# telemetry_adc.net
KiCad netlist of a schematic drawn in Altium Designer
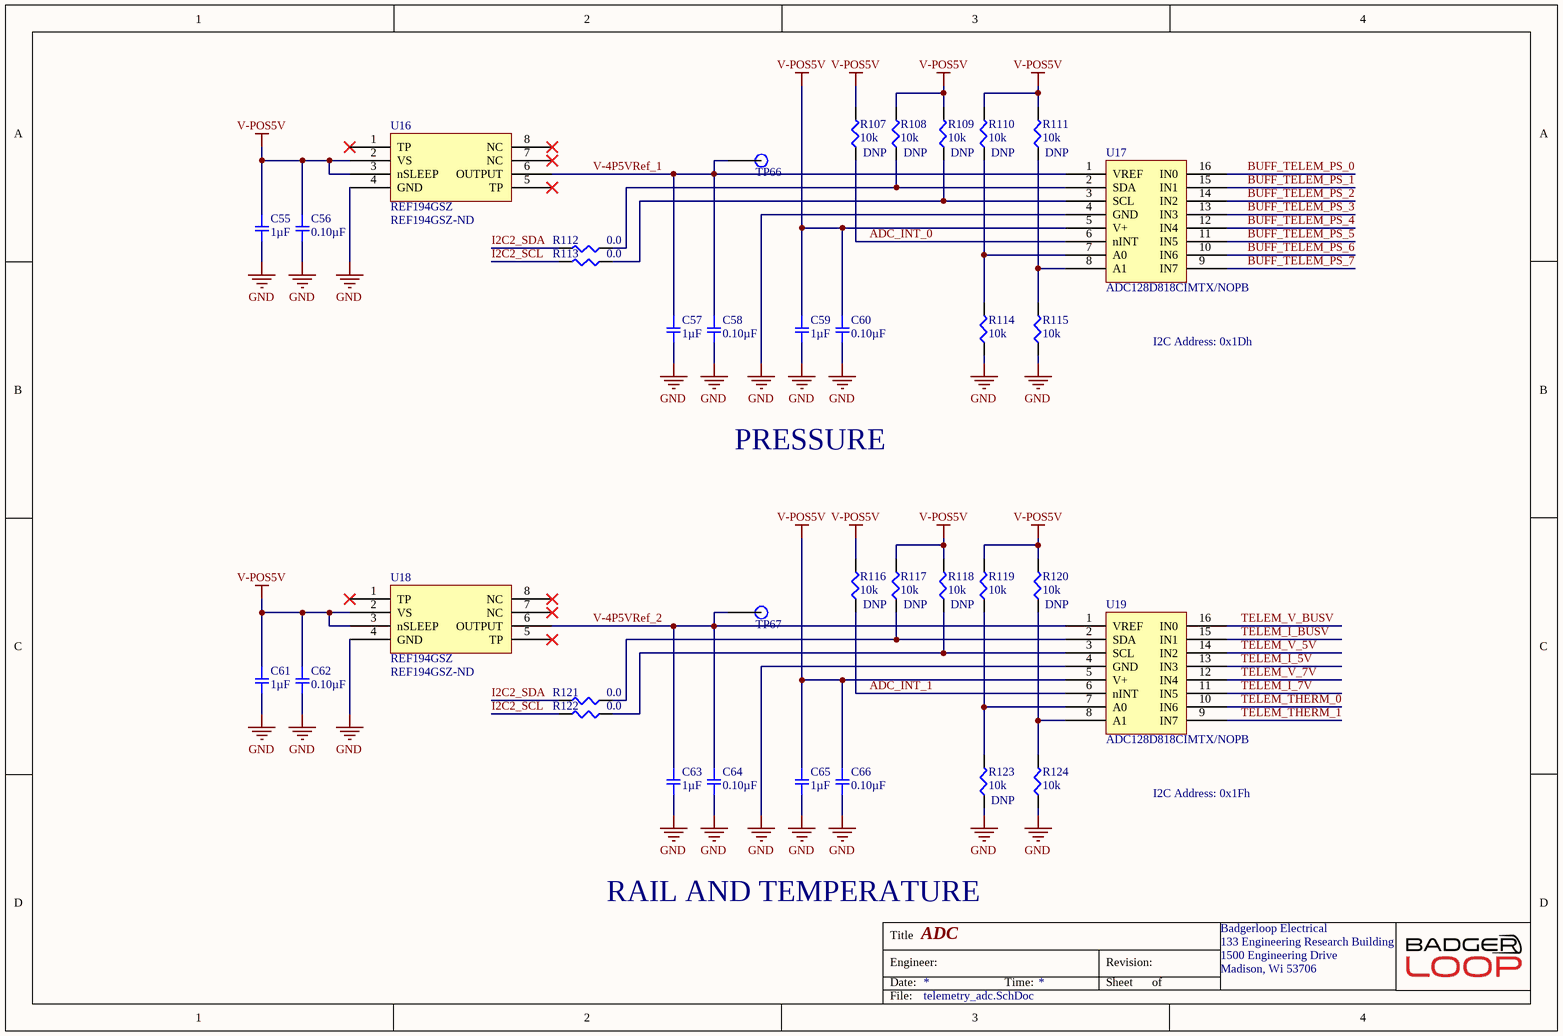
[diagram p0: telemetry_adc.SchDoc]

(export (version "E")
  (design (tool "Eeschema 10.0.6"))
  (components
    (comp (ref "C55")
      (value "1µF")
      (footprint "SMD-0805C")
      (description "CAP CER 1UF 50V X7R 0805")
      (fields
        (field (name "DIGI-KEY PART NUMBER") "490-4736-1-ND")
        (field (name "PART NUMBER") "GRM21BR71H105KA12L")
      )
      (libsource (lib "capacitors") (part "GRM21BR71H105KA12L"))
    )
    (comp (ref "C56")
      (value "0.10µF")
      (footprint "SMD-0805C")
      (description "CAP CER 0.1UF 50V X7R 0805")
      (fields
        (field (name "DIGI-KEY PART NUMBER") "490-11955-1-ND")
        (field (name "PART NUMBER") "GCD21BR71H104KA01L")
      )
      (libsource (lib "capacitors") (part "GCD21BR71H104KA01L"))
    )
    (comp (ref "C57")
      (value "1µF")
      (footprint "SMD-0805C")
      (description "CAP CER 1UF 50V X7R 0805")
      (fields
        (field (name "DIGI-KEY PART NUMBER") "490-4736-1-ND")
        (field (name "PART NUMBER") "GRM21BR71H105KA12L")
      )
      (libsource (lib "capacitors") (part "GRM21BR71H105KA12L"))
    )
    (comp (ref "C58")
      (value "0.10µF")
      (footprint "SMD-0805C")
      (description "CAP CER 0.1UF 50V X7R 0805")
      (fields
        (field (name "DIGI-KEY PART NUMBER") "490-11955-1-ND")
        (field (name "PART NUMBER") "GCD21BR71H104KA01L")
      )
      (libsource (lib "capacitors") (part "GCD21BR71H104KA01L"))
    )
    (comp (ref "C59")
      (value "1µF")
      (footprint "SMD-0805C")
      (description "CAP CER 1UF 50V X7R 0805")
      (fields
        (field (name "DIGI-KEY PART NUMBER") "490-4736-1-ND")
        (field (name "PART NUMBER") "GRM21BR71H105KA12L")
      )
      (libsource (lib "capacitors") (part "GRM21BR71H105KA12L"))
    )
    (comp (ref "C60")
      (value "0.10µF")
      (footprint "SMD-0805C")
      (description "CAP CER 0.1UF 50V X7R 0805")
      (fields
        (field (name "DIGI-KEY PART NUMBER") "490-11955-1-ND")
        (field (name "PART NUMBER") "GCD21BR71H104KA01L")
      )
      (libsource (lib "capacitors") (part "GCD21BR71H104KA01L"))
    )
    (comp (ref "C61")
      (value "1µF")
      (footprint "SMD-0805C")
      (description "CAP CER 1UF 50V X7R 0805")
      (fields
        (field (name "DIGI-KEY PART NUMBER") "490-4736-1-ND")
        (field (name "PART NUMBER") "GRM21BR71H105KA12L")
      )
      (libsource (lib "capacitors") (part "GRM21BR71H105KA12L"))
    )
    (comp (ref "C62")
      (value "0.10µF")
      (footprint "SMD-0805C")
      (description "CAP CER 0.1UF 50V X7R 0805")
      (fields
        (field (name "DIGI-KEY PART NUMBER") "490-11955-1-ND")
        (field (name "PART NUMBER") "GCD21BR71H104KA01L")
      )
      (libsource (lib "capacitors") (part "GCD21BR71H104KA01L"))
    )
    (comp (ref "C63")
      (value "1µF")
      (footprint "SMD-0805C")
      (description "CAP CER 1UF 50V X7R 0805")
      (fields
        (field (name "DIGI-KEY PART NUMBER") "490-4736-1-ND")
        (field (name "PART NUMBER") "GRM21BR71H105KA12L")
      )
      (libsource (lib "capacitors") (part "GRM21BR71H105KA12L"))
    )
    (comp (ref "C64")
      (value "0.10µF")
      (footprint "SMD-0805C")
      (description "CAP CER 0.1UF 50V X7R 0805")
      (fields
        (field (name "DIGI-KEY PART NUMBER") "490-11955-1-ND")
        (field (name "PART NUMBER") "GCD21BR71H104KA01L")
      )
      (libsource (lib "capacitors") (part "GCD21BR71H104KA01L"))
    )
    (comp (ref "C65")
      (value "1µF")
      (footprint "SMD-0805C")
      (description "CAP CER 1UF 50V X7R 0805")
      (fields
        (field (name "DIGI-KEY PART NUMBER") "490-4736-1-ND")
        (field (name "PART NUMBER") "GRM21BR71H105KA12L")
      )
      (libsource (lib "capacitors") (part "GRM21BR71H105KA12L"))
    )
    (comp (ref "C66")
      (value "0.10µF")
      (footprint "SMD-0805C")
      (description "CAP CER 0.1UF 50V X7R 0805")
      (fields
        (field (name "DIGI-KEY PART NUMBER") "490-11955-1-ND")
        (field (name "PART NUMBER") "GCD21BR71H104KA01L")
      )
      (libsource (lib "capacitors") (part "GCD21BR71H104KA01L"))
    )
    (comp (ref "R107")
      (value "10k")
      (footprint "SMD-0805-RES")
      (description "RES SMD 10K OHM 5% 1/2W 0805")
      (fields
        (field (name "PART NUMBER") "ERJ-P06J103V")
        (field (name "DIGI-KEY PART NUMBER") "P10KADCT-ND")
        (field (name "DNP") "DNP")
      )
      (libsource (lib "resistors") (part "ERJ-P06J103V"))
    )
    (comp (ref "R108")
      (value "10k")
      (footprint "SMD-0805-RES")
      (description "RES SMD 10K OHM 5% 1/2W 0805")
      (fields
        (field (name "PART NUMBER") "ERJ-P06J103V")
        (field (name "DIGI-KEY PART NUMBER") "P10KADCT-ND")
        (field (name "DNP") "DNP")
      )
      (libsource (lib "resistors") (part "ERJ-P06J103V"))
    )
    (comp (ref "R109")
      (value "10k")
      (footprint "SMD-0805-RES")
      (description "RES SMD 10K OHM 5% 1/2W 0805")
      (fields
        (field (name "PART NUMBER") "ERJ-P06J103V")
        (field (name "DIGI-KEY PART NUMBER") "P10KADCT-ND")
        (field (name "DNP") "DNP")
      )
      (libsource (lib "resistors") (part "ERJ-P06J103V"))
    )
    (comp (ref "R110")
      (value "10k")
      (footprint "SMD-0805-RES")
      (description "RES SMD 10K OHM 5% 1/2W 0805")
      (fields
        (field (name "PART NUMBER") "ERJ-P06J103V")
        (field (name "DIGI-KEY PART NUMBER") "P10KADCT-ND")
        (field (name "DNP") "DNP")
      )
      (libsource (lib "resistors") (part "ERJ-P06J103V"))
    )
    (comp (ref "R111")
      (value "10k")
      (footprint "SMD-0805-RES")
      (description "RES SMD 10K OHM 5% 1/2W 0805")
      (fields
        (field (name "PART NUMBER") "ERJ-P06J103V")
        (field (name "DIGI-KEY PART NUMBER") "P10KADCT-ND")
        (field (name "DNP") "DNP")
      )
      (libsource (lib "resistors") (part "ERJ-P06J103V"))
    )
    (comp (ref "R112")
      (value "0.0")
      (footprint "SMD-0805-RES")
      (description "RES SMD 0.0 OHM JUMPER 1/8W 0805")
      (fields (field (name "PART NUMBER") "ERJ-6GEY0R00V") (field (name "DIGI-KEY PART NUMBER") "P0.0ACT-ND"))
      (libsource (lib "resistors") (part "ERJ-6GEY0R00V"))
    )
    (comp (ref "R113")
      (value "0.0")
      (footprint "SMD-0805-RES")
      (description "RES SMD 0.0 OHM JUMPER 1/8W 0805")
      (fields (field (name "PART NUMBER") "ERJ-6GEY0R00V") (field (name "DIGI-KEY PART NUMBER") "P0.0ACT-ND"))
      (libsource (lib "resistors") (part "ERJ-6GEY0R00V"))
    )
    (comp (ref "R114")
      (value "10k")
      (footprint "SMD-0805-RES")
      (description "RES SMD 10K OHM 5% 1/2W 0805")
      (fields (field (name "PART NUMBER") "ERJ-P06J103V") (field (name "DIGI-KEY PART NUMBER") "P10KADCT-ND"))
      (libsource (lib "resistors") (part "ERJ-P06J103V"))
    )
    (comp (ref "R115")
      (value "10k")
      (footprint "SMD-0805-RES")
      (description "RES SMD 10K OHM 5% 1/2W 0805")
      (fields (field (name "PART NUMBER") "ERJ-P06J103V") (field (name "DIGI-KEY PART NUMBER") "P10KADCT-ND"))
      (libsource (lib "resistors") (part "ERJ-P06J103V"))
    )
    (comp (ref "R116")
      (value "10k")
      (footprint "SMD-0805-RES")
      (description "RES SMD 10K OHM 5% 1/2W 0805")
      (fields
        (field (name "PART NUMBER") "ERJ-P06J103V")
        (field (name "DIGI-KEY PART NUMBER") "P10KADCT-ND")
        (field (name "DNP") "DNP")
      )
      (libsource (lib "resistors") (part "ERJ-P06J103V"))
    )
    (comp (ref "R117")
      (value "10k")
      (footprint "SMD-0805-RES")
      (description "RES SMD 10K OHM 5% 1/2W 0805")
      (fields
        (field (name "PART NUMBER") "ERJ-P06J103V")
        (field (name "DIGI-KEY PART NUMBER") "P10KADCT-ND")
        (field (name "DNP") "DNP")
      )
      (libsource (lib "resistors") (part "ERJ-P06J103V"))
    )
    (comp (ref "R118")
      (value "10k")
      (footprint "SMD-0805-RES")
      (description "RES SMD 10K OHM 5% 1/2W 0805")
      (fields
        (field (name "PART NUMBER") "ERJ-P06J103V")
        (field (name "DIGI-KEY PART NUMBER") "P10KADCT-ND")
        (field (name "DNP") "DNP")
      )
      (libsource (lib "resistors") (part "ERJ-P06J103V"))
    )
    (comp (ref "R119")
      (value "10k")
      (footprint "SMD-0805-RES")
      (description "RES SMD 10K OHM 5% 1/2W 0805")
      (fields (field (name "PART NUMBER") "ERJ-P06J103V") (field (name "DIGI-KEY PART NUMBER") "P10KADCT-ND"))
      (libsource (lib "resistors") (part "ERJ-P06J103V"))
    )
    (comp (ref "R120")
      (value "10k")
      (footprint "SMD-0805-RES")
      (description "RES SMD 10K OHM 5% 1/2W 0805")
      (fields
        (field (name "PART NUMBER") "ERJ-P06J103V")
        (field (name "DIGI-KEY PART NUMBER") "P10KADCT-ND")
        (field (name "DNP") "DNP")
      )
      (libsource (lib "resistors") (part "ERJ-P06J103V"))
    )
    (comp (ref "R121")
      (value "0.0")
      (footprint "SMD-0805-RES")
      (description "RES SMD 0.0 OHM JUMPER 1/8W 0805")
      (fields (field (name "PART NUMBER") "ERJ-6GEY0R00V") (field (name "DIGI-KEY PART NUMBER") "P0.0ACT-ND"))
      (libsource (lib "resistors") (part "ERJ-6GEY0R00V"))
    )
    (comp (ref "R122")
      (value "0.0")
      (footprint "SMD-0805-RES")
      (description "RES SMD 0.0 OHM JUMPER 1/8W 0805")
      (fields (field (name "PART NUMBER") "ERJ-6GEY0R00V") (field (name "DIGI-KEY PART NUMBER") "P0.0ACT-ND"))
      (libsource (lib "resistors") (part "ERJ-6GEY0R00V"))
    )
    (comp (ref "R123")
      (value "10k")
      (footprint "SMD-0805-RES")
      (description "RES SMD 10K OHM 5% 1/2W 0805")
      (fields
        (field (name "PART NUMBER") "ERJ-P06J103V")
        (field (name "DIGI-KEY PART NUMBER") "P10KADCT-ND")
        (field (name "DNP") "DNP")
      )
      (libsource (lib "resistors") (part "ERJ-P06J103V"))
    )
    (comp (ref "R124")
      (value "10k")
      (footprint "SMD-0805-RES")
      (description "RES SMD 10K OHM 5% 1/2W 0805")
      (fields (field (name "PART NUMBER") "ERJ-P06J103V") (field (name "DIGI-KEY PART NUMBER") "P10KADCT-ND"))
      (libsource (lib "resistors") (part "ERJ-P06J103V"))
    )
    (comp (ref "TP66")
      (value "TP")
      (footprint "Test Point")
      (description "SMD TEST POINT")
      (libsource (lib "misc") (part "TP"))
    )
    (comp (ref "TP67")
      (value "TP")
      (footprint "Test Point")
      (description "SMD TEST POINT")
      (libsource (lib "misc") (part "TP"))
    )
    (comp (ref "U16")
      (value "REF194GSZ")
      (footprint "SOP127P600X175-8N")
      (description "IC VREF SERIES 4.5V 8SOIC")
      (fields
        (field (name "MANUFACTURER") "Analog Devices")
        (field (name "SUPPLIER PART NUMBER 1") "REF194GSZ-ND")
      )
      (libsource (lib "ic") (part "REF194GSZ"))
    )
    (comp (ref "U17")
      (value "ADC128D818CIMTX/NOPB")
      (footprint "TSOP65P660X120-16N")
      (description "Analog to Digital Converters - ADC")
      (fields (field (name "MANUFACTURER") "TI National Semiconductor"))
      (libsource (lib "ic") (part "ADC128D818CIMTX/NOPB"))
    )
    (comp (ref "U18")
      (value "REF194GSZ")
      (footprint "SOP127P600X175-8N")
      (description "IC VREF SERIES 4.5V 8SOIC")
      (fields
        (field (name "MANUFACTURER") "Analog Devices")
        (field (name "SUPPLIER PART NUMBER 1") "REF194GSZ-ND")
      )
      (libsource (lib "ic") (part "REF194GSZ"))
    )
    (comp (ref "U19")
      (value "ADC128D818CIMTX/NOPB")
      (footprint "TSOP65P660X120-16N")
      (description "Analog to Digital Converters - ADC")
      (fields (field (name "MANUFACTURER") "TI National Semiconductor"))
      (libsource (lib "ic") (part "ADC128D818CIMTX/NOPB"))
    )
  )
  (nets
    (net (code "1") (name "/ADC_INT_0") (class "Default")
      (node (ref "R107") (pin "1") (pinfunction "1_1") (pintype "passive"))
      (node (ref "U17") (pin "6") (pinfunction "nINT_6") (pintype "passive"))
    )
    (net (code "2") (name "/ADC_INT_1") (class "Default")
      (node (ref "R116") (pin "1") (pinfunction "1_1") (pintype "passive"))
      (node (ref "U19") (pin "6") (pinfunction "nINT_6") (pintype "passive"))
    )
    (net (code "3") (name "/BUFF_TELEM_PS_0") (class "Default")
      (node (ref "U17") (pin "16") (pinfunction "IN0_16") (pintype "passive"))
    )
    (net (code "4") (name "/BUFF_TELEM_PS_1") (class "Default")
      (node (ref "U17") (pin "15") (pinfunction "IN1_15") (pintype "passive"))
    )
    (net (code "5") (name "/BUFF_TELEM_PS_2") (class "Default")
      (node (ref "U17") (pin "14") (pinfunction "IN2_14") (pintype "passive"))
    )
    (net (code "6") (name "/BUFF_TELEM_PS_3") (class "Default")
      (node (ref "U17") (pin "13") (pinfunction "IN3_13") (pintype "passive"))
    )
    (net (code "7") (name "/BUFF_TELEM_PS_4") (class "Default")
      (node (ref "U17") (pin "12") (pinfunction "IN4_12") (pintype "passive"))
    )
    (net (code "8") (name "/BUFF_TELEM_PS_5") (class "Default")
      (node (ref "U17") (pin "11") (pinfunction "IN5_11") (pintype "passive"))
    )
    (net (code "9") (name "/BUFF_TELEM_PS_6") (class "Default")
      (node (ref "U17") (pin "10") (pinfunction "IN6_10") (pintype "passive"))
    )
    (net (code "10") (name "/BUFF_TELEM_PS_7") (class "Default")
      (node (ref "U17") (pin "9") (pinfunction "IN7_9") (pintype "passive"))
    )
    (net (code "11") (name "/I2C2_SCL") (class "Default")
      (node (ref "R113") (pin "2") (pinfunction "2_2") (pintype "passive"))
      (node (ref "R122") (pin "2") (pinfunction "2_2") (pintype "passive"))
    )
    (net (code "12") (name "/I2C2_SDA") (class "Default")
      (node (ref "R112") (pin "2") (pinfunction "2_2") (pintype "passive"))
      (node (ref "R121") (pin "2") (pinfunction "2_2") (pintype "passive"))
    )
    (net (code "13") (name "/TELEM_I_5V") (class "Default")
      (node (ref "U19") (pin "13") (pinfunction "IN3_13") (pintype "passive"))
    )
    (net (code "14") (name "/TELEM_I_7V") (class "Default")
      (node (ref "U19") (pin "11") (pinfunction "IN5_11") (pintype "passive"))
    )
    (net (code "15") (name "/TELEM_I_BUSV") (class "Default")
      (node (ref "U19") (pin "15") (pinfunction "IN1_15") (pintype "passive"))
    )
    (net (code "16") (name "/TELEM_THERM_0") (class "Default")
      (node (ref "U19") (pin "10") (pinfunction "IN6_10") (pintype "passive"))
    )
    (net (code "17") (name "/TELEM_THERM_1") (class "Default")
      (node (ref "U19") (pin "9") (pinfunction "IN7_9") (pintype "passive"))
    )
    (net (code "18") (name "/TELEM_V_5V") (class "Default")
      (node (ref "U19") (pin "14") (pinfunction "IN2_14") (pintype "passive"))
    )
    (net (code "19") (name "/TELEM_V_7V") (class "Default")
      (node (ref "U19") (pin "12") (pinfunction "IN4_12") (pintype "passive"))
    )
    (net (code "20") (name "/TELEM_V_BUSV") (class "Default")
      (node (ref "U19") (pin "16") (pinfunction "IN0_16") (pintype "passive"))
    )
    (net (code "21") (name "/V-4P5VRef_1") (class "Default")
      (node (ref "C57") (pin "1") (pinfunction "1_1") (pintype "passive"))
      (node (ref "C58") (pin "1") (pinfunction "1_1") (pintype "passive"))
      (node (ref "TP66") (pin "1") (pinfunction "1_1") (pintype "passive"))
      (node (ref "U16") (pin "6") (pinfunction "OUTPUT_6") (pintype "passive"))
      (node (ref "U17") (pin "1") (pinfunction "VREF_1") (pintype "passive"))
    )
    (net (code "22") (name "/V-4P5VRef_2") (class "Default")
      (node (ref "C63") (pin "1") (pinfunction "1_1") (pintype "passive"))
      (node (ref "C64") (pin "1") (pinfunction "1_1") (pintype "passive"))
      (node (ref "TP67") (pin "1") (pinfunction "1_1") (pintype "passive"))
      (node (ref "U18") (pin "6") (pinfunction "OUTPUT_6") (pintype "passive"))
      (node (ref "U19") (pin "1") (pinfunction "VREF_1") (pintype "passive"))
    )
    (net (code "23") (name "GND") (class "Default")
      (node (ref "C55") (pin "2") (pinfunction "2_2") (pintype "passive"))
      (node (ref "C56") (pin "2") (pinfunction "2_2") (pintype "passive"))
      (node (ref "C57") (pin "2") (pinfunction "2_2") (pintype "passive"))
      (node (ref "C58") (pin "2") (pinfunction "2_2") (pintype "passive"))
      (node (ref "C59") (pin "2") (pinfunction "2_2") (pintype "passive"))
      (node (ref "C60") (pin "2") (pinfunction "2_2") (pintype "passive"))
      (node (ref "C61") (pin "2") (pinfunction "2_2") (pintype "passive"))
      (node (ref "C62") (pin "2") (pinfunction "2_2") (pintype "passive"))
      (node (ref "C63") (pin "2") (pinfunction "2_2") (pintype "passive"))
      (node (ref "C64") (pin "2") (pinfunction "2_2") (pintype "passive"))
      (node (ref "C65") (pin "2") (pinfunction "2_2") (pintype "passive"))
      (node (ref "C66") (pin "2") (pinfunction "2_2") (pintype "passive"))
      (node (ref "R114") (pin "1") (pinfunction "1_1") (pintype "passive"))
      (node (ref "R115") (pin "1") (pinfunction "1_1") (pintype "passive"))
      (node (ref "R123") (pin "1") (pinfunction "1_1") (pintype "passive"))
      (node (ref "R124") (pin "1") (pinfunction "1_1") (pintype "passive"))
      (node (ref "U16") (pin "4") (pinfunction "GND_4") (pintype "passive"))
      (node (ref "U17") (pin "4") (pinfunction "GND_4") (pintype "passive"))
      (node (ref "U18") (pin "4") (pinfunction "GND_4") (pintype "passive"))
      (node (ref "U19") (pin "4") (pinfunction "GND_4") (pintype "passive"))
    )
    (net (code "24") (name "Net-(U17-A0)") (class "Default")
      (node (ref "R110") (pin "1") (pinfunction "1_1") (pintype "passive"))
      (node (ref "R114") (pin "2") (pinfunction "2_2") (pintype "passive"))
      (node (ref "U17") (pin "7") (pinfunction "A0_7") (pintype "passive"))
    )
    (net (code "25") (name "Net-(U17-A1)") (class "Default")
      (node (ref "R111") (pin "1") (pinfunction "1_1") (pintype "passive"))
      (node (ref "R115") (pin "2") (pinfunction "2_2") (pintype "passive"))
      (node (ref "U17") (pin "8") (pinfunction "A1_8") (pintype "passive"))
    )
    (net (code "26") (name "Net-(U17-SCL)") (class "Default")
      (node (ref "R109") (pin "1") (pinfunction "1_1") (pintype "passive"))
      (node (ref "R113") (pin "1") (pinfunction "1_1") (pintype "passive"))
      (node (ref "U17") (pin "3") (pinfunction "SCL_3") (pintype "passive"))
    )
    (net (code "27") (name "Net-(U17-SDA)") (class "Default")
      (node (ref "R108") (pin "1") (pinfunction "1_1") (pintype "passive"))
      (node (ref "R112") (pin "1") (pinfunction "1_1") (pintype "passive"))
      (node (ref "U17") (pin "2") (pinfunction "SDA_2") (pintype "passive"))
    )
    (net (code "28") (name "Net-(U19-A0)") (class "Default")
      (node (ref "R119") (pin "1") (pinfunction "1_1") (pintype "passive"))
      (node (ref "R123") (pin "2") (pinfunction "2_2") (pintype "passive"))
      (node (ref "U19") (pin "7") (pinfunction "A0_7") (pintype "passive"))
    )
    (net (code "29") (name "Net-(U19-A1)") (class "Default")
      (node (ref "R120") (pin "1") (pinfunction "1_1") (pintype "passive"))
      (node (ref "R124") (pin "2") (pinfunction "2_2") (pintype "passive"))
      (node (ref "U19") (pin "8") (pinfunction "A1_8") (pintype "passive"))
    )
    (net (code "30") (name "Net-(U19-SCL)") (class "Default")
      (node (ref "R118") (pin "1") (pinfunction "1_1") (pintype "passive"))
      (node (ref "R122") (pin "1") (pinfunction "1_1") (pintype "passive"))
      (node (ref "U19") (pin "3") (pinfunction "SCL_3") (pintype "passive"))
    )
    (net (code "31") (name "Net-(U19-SDA)") (class "Default")
      (node (ref "R117") (pin "1") (pinfunction "1_1") (pintype "passive"))
      (node (ref "R121") (pin "1") (pinfunction "1_1") (pintype "passive"))
      (node (ref "U19") (pin "2") (pinfunction "SDA_2") (pintype "passive"))
    )
    (net (code "32") (name "V-POS5V") (class "Default")
      (node (ref "C55") (pin "1") (pinfunction "1_1") (pintype "passive"))
      (node (ref "C56") (pin "1") (pinfunction "1_1") (pintype "passive"))
      (node (ref "C59") (pin "1") (pinfunction "1_1") (pintype "passive"))
      (node (ref "C60") (pin "1") (pinfunction "1_1") (pintype "passive"))
      (node (ref "C61") (pin "1") (pinfunction "1_1") (pintype "passive"))
      (node (ref "C62") (pin "1") (pinfunction "1_1") (pintype "passive"))
      (node (ref "C65") (pin "1") (pinfunction "1_1") (pintype "passive"))
      (node (ref "C66") (pin "1") (pinfunction "1_1") (pintype "passive"))
      (node (ref "R107") (pin "2") (pinfunction "2_2") (pintype "passive"))
      (node (ref "R108") (pin "2") (pinfunction "2_2") (pintype "passive"))
      (node (ref "R109") (pin "2") (pinfunction "2_2") (pintype "passive"))
      (node (ref "R110") (pin "2") (pinfunction "2_2") (pintype "passive"))
      (node (ref "R111") (pin "2") (pinfunction "2_2") (pintype "passive"))
      (node (ref "R116") (pin "2") (pinfunction "2_2") (pintype "passive"))
      (node (ref "R117") (pin "2") (pinfunction "2_2") (pintype "passive"))
      (node (ref "R118") (pin "2") (pinfunction "2_2") (pintype "passive"))
      (node (ref "R119") (pin "2") (pinfunction "2_2") (pintype "passive"))
      (node (ref "R120") (pin "2") (pinfunction "2_2") (pintype "passive"))
      (node (ref "U16") (pin "2") (pinfunction "VS_2") (pintype "passive"))
      (node (ref "U16") (pin "3") (pinfunction "nSLEEP_3") (pintype "passive"))
      (node (ref "U17") (pin "5") (pinfunction "V+_5") (pintype "passive"))
      (node (ref "U18") (pin "2") (pinfunction "VS_2") (pintype "passive"))
      (node (ref "U18") (pin "3") (pinfunction "nSLEEP_3") (pintype "passive"))
      (node (ref "U19") (pin "5") (pinfunction "V+_5") (pintype "passive"))
    )
    (net (code "33") (name "unconnected-(U16-NC-Pad7)") (class "Default")
      (node (ref "U16") (pin "7") (pinfunction "NC_7") (pintype "passive+no_connect"))
    )
    (net (code "34") (name "unconnected-(U16-NC-Pad8)") (class "Default")
      (node (ref "U16") (pin "8") (pinfunction "NC_8") (pintype "passive+no_connect"))
    )
    (net (code "35") (name "unconnected-(U16-TP-Pad1)") (class "Default")
      (node (ref "U16") (pin "1") (pinfunction "TP_1") (pintype "passive+no_connect"))
    )
    (net (code "36") (name "unconnected-(U16-TP-Pad5)") (class "Default")
      (node (ref "U16") (pin "5") (pinfunction "TP_5") (pintype "passive+no_connect"))
    )
    (net (code "37") (name "unconnected-(U18-NC-Pad7)") (class "Default")
      (node (ref "U18") (pin "7") (pinfunction "NC_7") (pintype "passive+no_connect"))
    )
    (net (code "38") (name "unconnected-(U18-NC-Pad8)") (class "Default")
      (node (ref "U18") (pin "8") (pinfunction "NC_8") (pintype "passive+no_connect"))
    )
    (net (code "39") (name "unconnected-(U18-TP-Pad1)") (class "Default")
      (node (ref "U18") (pin "1") (pinfunction "TP_1") (pintype "passive+no_connect"))
    )
    (net (code "40") (name "unconnected-(U18-TP-Pad5)") (class "Default")
      (node (ref "U18") (pin "5") (pinfunction "TP_5") (pintype "passive+no_connect"))
    )
  )
)
